# AnalogReceiverModule.net
KiCad netlist of a schematic drawn in Altium Designer
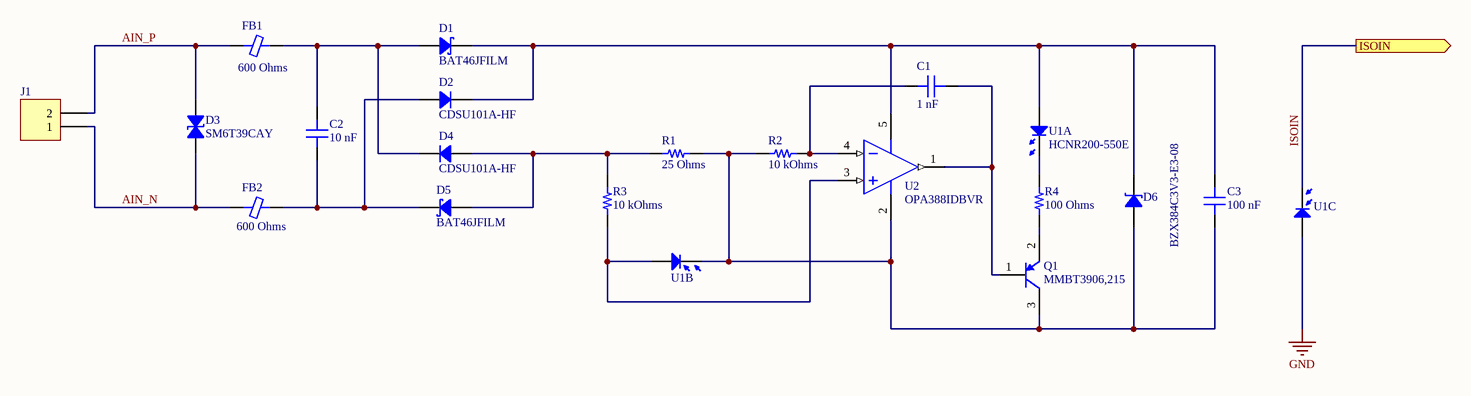
[diagram p0: AnalogReceiverModule.SchDoc]

(export (version "E")
  (design (tool "Eeschema 10.0.6"))
  (components
    (comp (ref "C1")
      (value "1 nF")
      (footprint "CAP 0805_2012")
      (description "MLCC Ceramic 1 nF 200 V 5% Capacitor")
      (fields (field (name "PART NUMBER") "C0805C102J2GECAUTO") (field (name "MANUFACTURER") "KEMET"))
      (libsource (lib "Database_Libs") (part "Capacitor"))
    )
    (comp (ref "C2")
      (value "10 nF")
      (footprint "CAP 0805_2012")
      (description "MLCC Ceramic 10 nF 50 V 10% Capacitor")
      (fields (field (name "PART NUMBER") "C0805C103K5GEC7210") (field (name "MANUFACTURER") "KEMET"))
      (libsource (lib "Database_Libs") (part "Capacitor"))
    )
    (comp (ref "C3")
      (value "100 nF")
      (footprint "CAP 0805_2012")
      (description "MLCC Ceramic 100 nF 50 V 10% Capacitor")
      (fields (field (name "PART NUMBER") "08055C104K4Z2A") (field (name "MANUFACTURER") "AVX"))
      (libsource (lib "Database_Libs") (part "Capacitor"))
    )
    (comp (ref "D1")
      (value "BAT46JFILM")
      (footprint "SOD323")
      (description "Schottky Diode")
      (fields (field (name "MANUFACTURER") "STMicroelectronics"))
      (libsource (lib "Database_Libs") (part "Schottky"))
    )
    (comp (ref "D2")
      (value "CDSU101A-HF")
      (footprint "SOD523F")
      (description "General Purpose Diode")
      (fields (field (name "MANUFACTURER") "Comchip Technology"))
      (libsource (lib "Database_Libs") (part "Diode"))
    )
    (comp (ref "D3")
      (value "SM6T39CAY")
      (footprint "DO214AA SMB")
      (description "TVS Diode")
      (fields (field (name "MANUFACTURER") "STMicroelectronics"))
      (libsource (lib "Database_Libs") (part "Diode TVS"))
    )
    (comp (ref "D4")
      (value "CDSU101A-HF")
      (footprint "SOD523F")
      (description "General Purpose Diode")
      (fields (field (name "MANUFACTURER") "Comchip Technology"))
      (libsource (lib "Database_Libs") (part "Diode"))
    )
    (comp (ref "D5")
      (value "BAT46JFILM")
      (footprint "SOD323")
      (description "Schottky Diode")
      (fields (field (name "MANUFACTURER") "STMicroelectronics"))
      (libsource (lib "Database_Libs") (part "Schottky"))
    )
    (comp (ref "D6")
      (value "BZX384C3V3-E3-08")
      (footprint "SOD323")
      (description "Zener Diode 3.3 V 200 mW")
      (fields (field (name "MANUFACTURER") "Vishay") (field (name "TOLERANCE") "5%"))
      (libsource (lib "Database_Libs") (part "Diode Zener"))
    )
    (comp (ref "FB1")
      (value "600 Ohms")
      (footprint "FER 0805_2012")
      (description "Ferrite bead")
      (fields
        (field (name "PART NUMBER") "BLM21SP601SH1D")
        (field (name "MANUFACTURER") "Murata Electronics")
      )
      (libsource (lib "Database_Libs") (part "Ferrite Chip"))
    )
    (comp (ref "FB2")
      (value "600 Ohms")
      (footprint "FER 0805_2012")
      (description "Ferrite bead")
      (fields
        (field (name "PART NUMBER") "BLM21SP601SH1D")
        (field (name "MANUFACTURER") "Murata Electronics")
      )
      (libsource (lib "Database_Libs") (part "Ferrite Chip"))
    )
    (comp (ref "J1")
      (value "1757475")
      (footprint "MSTBA2")
      (description "Pluggable Terminal Blocks 2 Pos 5mm pitch Through Hole Header")
      (fields (field (name "MANUFACTURER") "Phoenix Contact") (field (name "PUBLISHER") "Altium Limited"))
      (libsource (lib "Database_Libs") (part "GEN-2-CON"))
    )
    (comp (ref "Q1")
      (value "MMBT3906,215")
      (footprint "NEXPERIA SOT-23-3")
      (description "PNP BJT Switching transistor")
      (fields (field (name "MANUFACTURER") "Nexperia"))
      (libsource (lib "Database_Libs") (part "PNP SOT-23-3"))
    )
    (comp (ref "R1")
      (value "25 Ohms")
      (footprint "RES 0805_2012")
      (description "Thin Film Resistor 25 Ohms 0.1%")
      (fields (field (name "PART NUMBER") "PAT0805E25R0BST1") (field (name "MANUFACTURER") "Vishay"))
      (libsource (lib "Database_Libs") (part "Resistor"))
    )
    (comp (ref "R2")
      (value "10 kOhms")
      (footprint "RES 0805_2012")
      (description "Thin Film Resistor 10 kOhms 1%")
      (fields (field (name "PART NUMBER") "CRCW080510K0FKEAC") (field (name "MANUFACTURER") "Vishay / Dale"))
      (libsource (lib "Database_Libs") (part "Resistor"))
    )
    (comp (ref "R3")
      (value "10 kOhms")
      (footprint "RES 0805_2012")
      (description "Thin Film Resistor 10 kOhms 1%")
      (fields (field (name "PART NUMBER") "CRCW080510K0FKEAC") (field (name "MANUFACTURER") "Vishay / Dale"))
      (libsource (lib "Database_Libs") (part "Resistor"))
    )
    (comp (ref "R4")
      (value "100 Ohms")
      (footprint "RES 0805_2012")
      (description "Thin Film Resistor 100 Ohms 1%")
      (fields (field (name "PART NUMBER") "CRCW0805100RFKEAC") (field (name "MANUFACTURER") "Vishay / Dale"))
      (libsource (lib "Database_Libs") (part "Resistor"))
    )
    (comp (ref "U1")
      (value "HCNR200-550E")
      (footprint "HCNR200")
      (description "HCNR200 High-Linearity Analog Optocoupler")
      (fields (field (name "MANUFACTURER") "Broadcom / Avago"))
      (libsource (lib "Database_Libs") (part "LINEAR OPTOCOUPLER"))
    )
    (comp (ref "U2")
      (value "OPA388IDBVR")
      (footprint "TI SOT-23-5 DBV")
      (description "OPA388 Zero-Drift, Zero-Crossover, Low Offset, Precision Rail-to-Rail I/O Opamp")
      (fields (field (name "MANUFACTURER") "Texas Instruments"))
      (libsource (lib "Database_Libs") (part "OPA388"))
    )
  )
  (nets
    (net (code "1") (name "/AIN_N") (class "Default")
      (node (ref "D3") (pin "2") (pinfunction "2_2") (pintype "passive"))
      (node (ref "FB2") (pin "2") (pinfunction "2_2") (pintype "passive"))
      (node (ref "J1") (pin "1") (pinfunction "1_1") (pintype "passive"))
    )
    (net (code "2") (name "/AIN_P") (class "Default")
      (node (ref "D3") (pin "1") (pinfunction "1_1") (pintype "passive"))
      (node (ref "FB1") (pin "1") (pinfunction "1_1") (pintype "passive"))
      (node (ref "J1") (pin "2") (pinfunction "2_2") (pintype "passive"))
    )
    (net (code "3") (name "/ISOIN") (class "Default")
      (node (ref "U1") (pin "6") (pinfunction "PD2_A_6") (pintype "passive"))
    )
    (net (code "4") (name "GND") (class "Default")
      (node (ref "U1") (pin "5") (pinfunction "PD2_B_5") (pintype "passive"))
    )
    (net (code "5") (name "Net-(C2-Pad1)") (class "Default")
      (node (ref "C2") (pin "1") (pinfunction "1_1") (pintype "passive"))
      (node (ref "D2") (pin "1") (pinfunction "1_1") (pintype "passive"))
      (node (ref "D5") (pin "2") (pinfunction "2_2") (pintype "passive"))
      (node (ref "FB2") (pin "1") (pinfunction "1_1") (pintype "passive"))
    )
    (net (code "6") (name "Net-(C2-Pad2)") (class "Default")
      (node (ref "C2") (pin "2") (pinfunction "2_2") (pintype "passive"))
      (node (ref "D1") (pin "1") (pinfunction "1_1") (pintype "passive"))
      (node (ref "D4") (pin "2") (pinfunction "2_2") (pintype "passive"))
      (node (ref "FB1") (pin "2") (pinfunction "2_2") (pintype "passive"))
    )
    (net (code "7") (name "Net-(D4-Pad1)") (class "Default")
      (node (ref "D4") (pin "1") (pinfunction "1_1") (pintype "passive"))
      (node (ref "D5") (pin "1") (pinfunction "1_1") (pintype "passive"))
      (node (ref "R1") (pin "1") (pinfunction "1_1") (pintype "passive"))
      (node (ref "R3") (pin "1") (pinfunction "1_1") (pintype "passive"))
    )
    (net (code "8") (name "Net-(Q1-B)") (class "Default")
      (node (ref "C1") (pin "1") (pinfunction "1_1") (pintype "passive"))
      (node (ref "Q1") (pin "1") (pinfunction "B_1") (pintype "passive"))
      (node (ref "U2") (pin "1") (pinfunction "OUT_1") (pintype "output"))
    )
    (net (code "9") (name "Net-(Q1-C)") (class "Default")
      (node (ref "C3") (pin "1") (pinfunction "1_1") (pintype "passive"))
      (node (ref "D6") (pin "1") (pinfunction "1_1") (pintype "passive"))
      (node (ref "Q1") (pin "3") (pinfunction "C_3") (pintype "passive"))
      (node (ref "R1") (pin "2") (pinfunction "2_2") (pintype "passive"))
      (node (ref "R2") (pin "2") (pinfunction "2_2") (pintype "passive"))
      (node (ref "U1") (pin "3") (pinfunction "PD1_A_3") (pintype "passive"))
      (node (ref "U2") (pin "2") (pinfunction "GND_2") (pintype "power_in"))
    )
    (net (code "10") (name "Net-(Q1-E)") (class "Default")
      (node (ref "Q1") (pin "2") (pinfunction "E_2") (pintype "passive"))
      (node (ref "R4") (pin "2") (pinfunction "2_2") (pintype "passive"))
    )
    (net (code "11") (name "Net-(U1A-LED_1)") (class "Default")
      (node (ref "R4") (pin "1") (pinfunction "1_1") (pintype "passive"))
      (node (ref "U1") (pin "1") (pinfunction "LED_1_1") (pintype "passive"))
    )
    (net (code "12") (name "Net-(U1A-LED_2)") (class "Default")
      (node (ref "C3") (pin "2") (pinfunction "2_2") (pintype "passive"))
      (node (ref "D1") (pin "2") (pinfunction "2_2") (pintype "passive"))
      (node (ref "D2") (pin "2") (pinfunction "2_2") (pintype "passive"))
      (node (ref "D6") (pin "2") (pinfunction "2_2") (pintype "passive"))
      (node (ref "U1") (pin "2") (pinfunction "LED_2_2") (pintype "passive"))
      (node (ref "U2") (pin "5") (pinfunction "VDD_5") (pintype "power_in"))
    )
    (net (code "13") (name "Net-(U1B-PD1_B)") (class "Default")
      (node (ref "R3") (pin "2") (pinfunction "2_2") (pintype "passive"))
      (node (ref "U1") (pin "4") (pinfunction "PD1_B_4") (pintype "passive"))
      (node (ref "U2") (pin "3") (pinfunction "IN+_3") (pintype "input"))
    )
    (net (code "14") (name "Net-(U2-IN-)") (class "Default")
      (node (ref "C1") (pin "2") (pinfunction "2_2") (pintype "passive"))
      (node (ref "R2") (pin "1") (pinfunction "1_1") (pintype "passive"))
      (node (ref "U2") (pin "4") (pinfunction "IN-_4") (pintype "input"))
    )
  )
)
